# LCD.net
KiCad netlist of a schematic drawn in Altium Designer
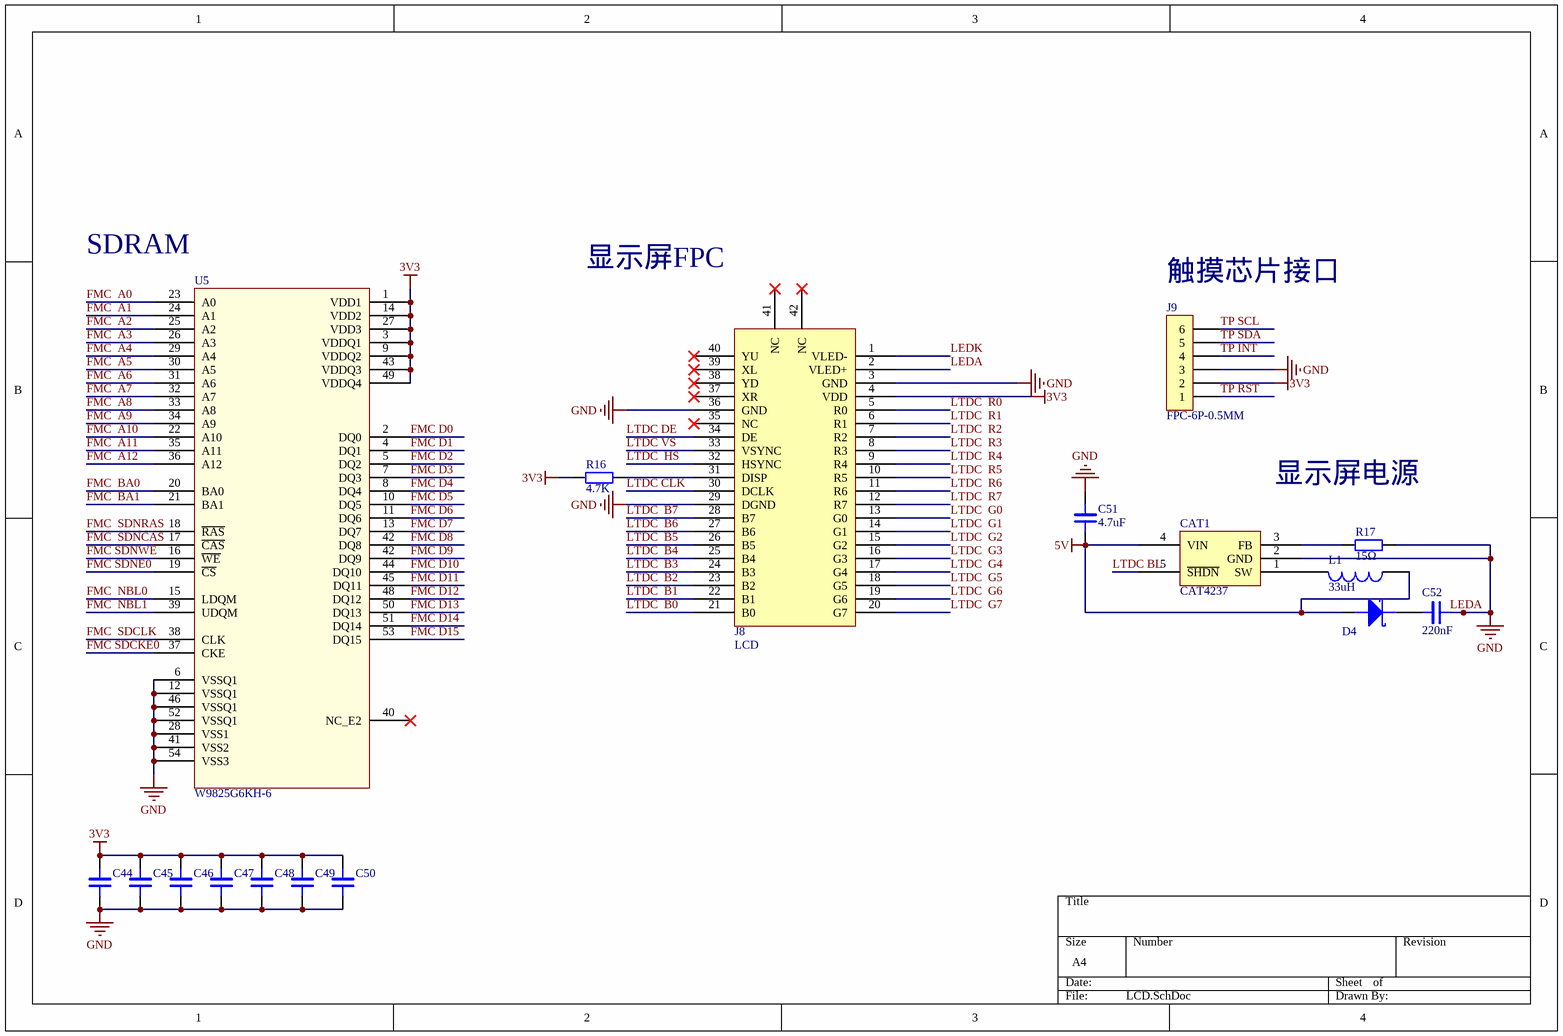
[diagram p0: LCD.SchDoc]

(export (version "E")
  (design (tool "Eeschema 10.0.6"))
  (components
    (comp (ref "C44")
      (value "100nF 16V")
      (footprint "0805")
      (description "Capacitor")
      (libsource (lib "General") (part "CAP"))
    )
    (comp (ref "C45")
      (value "100nF 16V")
      (footprint "0805")
      (description "Capacitor")
      (libsource (lib "General") (part "CAP"))
    )
    (comp (ref "C46")
      (value "100nF 16V")
      (footprint "0805")
      (description "Capacitor")
      (libsource (lib "General") (part "CAP"))
    )
    (comp (ref "C47")
      (value "100nF 16V")
      (footprint "0805")
      (description "Capacitor")
      (libsource (lib "General") (part "CAP"))
    )
    (comp (ref "C48")
      (value "100nF 16V")
      (footprint "0805")
      (description "Capacitor")
      (libsource (lib "General") (part "CAP"))
    )
    (comp (ref "C49")
      (value "100nF 16V")
      (footprint "0805")
      (description "Capacitor")
      (libsource (lib "General") (part "CAP"))
    )
    (comp (ref "C50")
      (value "100nF 16V")
      (footprint "0805")
      (description "Capacitor")
      (libsource (lib "General") (part "CAP"))
    )
    (comp (ref "C51")
      (value "4.7uF")
      (footprint "CAP-1812")
      (description "Capacitor")
      (libsource (lib "General") (part "CAP"))
    )
    (comp (ref "C52")
      (value "220nF")
      (footprint "CAP-1812")
      (description "Capacitor")
      (libsource (lib "General") (part "CAP"))
    )
    (comp (ref "CAT1")
      (value "CAT4237")
      (footprint "SOT-23-5")
      (libsource (lib "MainBoard") (part "CAT4237"))
    )
    (comp (ref "D4")
      (value "~")
      (footprint "DO-15")
      (description "肖特基二极管")
      (libsource (lib "二极管") (part "DIODE SCHOTTKY"))
    )
    (comp (ref "J8")
      (value "LCD")
      (description "FPC 接线口0.5mm 40Pins")
      (libsource (lib "MainBoard") (part "LCD"))
    )
    (comp (ref "J9")
      (value "FPC-6P-0.5MM")
      (footprint "Pin HDR1X6/2.54mm-S")
      (libsource (lib "排针") (part "Pin HDR1X6"))
    )
    (comp (ref "L1")
      (value "33uH")
      (footprint "AL0204")
      (description "INDUCTOR")
      (libsource (lib "电感") (part "INDUCTOR"))
    )
    (comp (ref "R16")
      (value "4.7K")
      (footprint "0805")
      (description "Resistor")
      (libsource (lib "General") (part "RES"))
    )
    (comp (ref "R17")
      (value "15Ω")
      (footprint "0805")
      (description "Resistor")
      (libsource (lib "General") (part "RES"))
    )
    (comp (ref "U5") (value "W9825G6KH-6") (libsource (lib "MainBoard") (part "W9825G6KH-6")))
  )
  (nets
    (net (code "1") (name "/FMC  A0") (class "Default")
      (node (ref "U5") (pin "23") (pinfunction "A0_23") (pintype "passive"))
    )
    (net (code "2") (name "/FMC  A1") (class "Default")
      (node (ref "U5") (pin "24") (pinfunction "A1_24") (pintype "passive"))
    )
    (net (code "3") (name "/FMC  A2") (class "Default")
      (node (ref "U5") (pin "25") (pinfunction "A2_25") (pintype "passive"))
    )
    (net (code "4") (name "/FMC  A3") (class "Default")
      (node (ref "U5") (pin "26") (pinfunction "A3_26") (pintype "passive"))
    )
    (net (code "5") (name "/FMC  A4") (class "Default")
      (node (ref "U5") (pin "29") (pinfunction "A4_29") (pintype "passive"))
    )
    (net (code "6") (name "/FMC  A5") (class "Default")
      (node (ref "U5") (pin "30") (pinfunction "A5_30") (pintype "passive"))
    )
    (net (code "7") (name "/FMC  A6") (class "Default")
      (node (ref "U5") (pin "31") (pinfunction "A6_31") (pintype "passive"))
    )
    (net (code "8") (name "/FMC  A7") (class "Default")
      (node (ref "U5") (pin "32") (pinfunction "A7_32") (pintype "passive"))
    )
    (net (code "9") (name "/FMC  A8") (class "Default")
      (node (ref "U5") (pin "33") (pinfunction "A8_33") (pintype "passive"))
    )
    (net (code "10") (name "/FMC  A9") (class "Default")
      (node (ref "U5") (pin "34") (pinfunction "A9_34") (pintype "passive"))
    )
    (net (code "11") (name "/FMC  A10") (class "Default")
      (node (ref "U5") (pin "22") (pinfunction "A10_22") (pintype "passive"))
    )
    (net (code "12") (name "/FMC  A11") (class "Default")
      (node (ref "U5") (pin "35") (pinfunction "A11_35") (pintype "passive"))
    )
    (net (code "13") (name "/FMC  A12") (class "Default")
      (node (ref "U5") (pin "36") (pinfunction "A12_36") (pintype "passive"))
    )
    (net (code "14") (name "/FMC  BA0") (class "Default")
      (node (ref "U5") (pin "20") (pinfunction "BA0_20") (pintype "passive"))
    )
    (net (code "15") (name "/FMC  BA1") (class "Default")
      (node (ref "U5") (pin "21") (pinfunction "BA1_21") (pintype "passive"))
    )
    (net (code "16") (name "/FMC  NBL0") (class "Default")
      (node (ref "U5") (pin "15") (pinfunction "LDQM_15") (pintype "passive"))
    )
    (net (code "17") (name "/FMC  NBL1") (class "Default")
      (node (ref "U5") (pin "39") (pinfunction "UDQM_39") (pintype "passive"))
    )
    (net (code "18") (name "/FMC  SDCLK") (class "Default")
      (node (ref "U5") (pin "38") (pinfunction "CLK_38") (pintype "passive"))
    )
    (net (code "19") (name "/FMC  SDNCAS") (class "Default")
      (node (ref "U5") (pin "17") (pinfunction "~{CAS}_17") (pintype "passive"))
    )
    (net (code "20") (name "/FMC  SDNRAS") (class "Default")
      (node (ref "U5") (pin "18") (pinfunction "~{RAS}_18") (pintype "passive"))
    )
    (net (code "21") (name "/FMC D0") (class "Default")
      (node (ref "U5") (pin "2") (pinfunction "DQ0_2") (pintype "passive"))
    )
    (net (code "22") (name "/FMC D1") (class "Default")
      (node (ref "U5") (pin "4") (pinfunction "DQ1_4") (pintype "passive"))
    )
    (net (code "23") (name "/FMC D2") (class "Default")
      (node (ref "U5") (pin "5") (pinfunction "DQ2_5") (pintype "passive"))
    )
    (net (code "24") (name "/FMC D3") (class "Default")
      (node (ref "U5") (pin "7") (pinfunction "DQ3_7") (pintype "passive"))
    )
    (net (code "25") (name "/FMC D4") (class "Default")
      (node (ref "U5") (pin "8") (pinfunction "DQ4_8") (pintype "passive"))
    )
    (net (code "26") (name "/FMC D5") (class "Default")
      (node (ref "U5") (pin "10") (pinfunction "DQ5_10") (pintype "passive"))
    )
    (net (code "27") (name "/FMC D6") (class "Default")
      (node (ref "U5") (pin "11") (pinfunction "DQ6_11") (pintype "passive"))
    )
    (net (code "28") (name "/FMC D7") (class "Default")
      (node (ref "U5") (pin "13") (pinfunction "DQ7_13") (pintype "passive"))
    )
    (net (code "29") (name "/FMC D8") (class "Default")
      (node (ref "U5") (pin "42") (pinfunction "DQ8_42") (pintype "passive"))
    )
    (net (code "30") (name "/FMC D9") (class "Default")
      (node (ref "U5") (pin "42") (pinfunction "DQ9_42") (pintype "passive"))
    )
    (net (code "31") (name "/FMC D10") (class "Default")
      (node (ref "U5") (pin "44") (pinfunction "DQ10_44") (pintype "passive"))
    )
    (net (code "32") (name "/FMC D11") (class "Default")
      (node (ref "U5") (pin "45") (pinfunction "DQ11_45") (pintype "passive"))
    )
    (net (code "33") (name "/FMC D12") (class "Default")
      (node (ref "U5") (pin "48") (pinfunction "DQ12_48") (pintype "passive"))
    )
    (net (code "34") (name "/FMC D13") (class "Default")
      (node (ref "U5") (pin "50") (pinfunction "DQ13_50") (pintype "passive"))
    )
    (net (code "35") (name "/FMC D14") (class "Default")
      (node (ref "U5") (pin "51") (pinfunction "DQ14_51") (pintype "passive"))
    )
    (net (code "36") (name "/FMC D15") (class "Default")
      (node (ref "U5") (pin "53") (pinfunction "DQ15_53") (pintype "passive"))
    )
    (net (code "37") (name "/FMC SDCKE0") (class "Default")
      (node (ref "U5") (pin "37") (pinfunction "CKE_37") (pintype "passive"))
    )
    (net (code "38") (name "/FMC SDNE0") (class "Default")
      (node (ref "U5") (pin "19") (pinfunction "~{CS}_19") (pintype "passive"))
    )
    (net (code "39") (name "/FMC SDNWE") (class "Default")
      (node (ref "U5") (pin "16") (pinfunction "~{WE}_16") (pintype "passive"))
    )
    (net (code "40") (name "/LEDK") (class "Default")
      (node (ref "J8") (pin "1") (pinfunction "VLED-_1") (pintype "passive"))
    )
    (net (code "41") (name "/LTDC  B0") (class "Default")
      (node (ref "J8") (pin "21") (pinfunction "B0_21") (pintype "passive"))
    )
    (net (code "42") (name "/LTDC  B1") (class "Default")
      (node (ref "J8") (pin "22") (pinfunction "B1_22") (pintype "passive"))
    )
    (net (code "43") (name "/LTDC  B2") (class "Default")
      (node (ref "J8") (pin "23") (pinfunction "B2_23") (pintype "passive"))
    )
    (net (code "44") (name "/LTDC  B3") (class "Default")
      (node (ref "J8") (pin "24") (pinfunction "B3_24") (pintype "passive"))
    )
    (net (code "45") (name "/LTDC  B4") (class "Default")
      (node (ref "J8") (pin "25") (pinfunction "B4_25") (pintype "passive"))
    )
    (net (code "46") (name "/LTDC  B5") (class "Default")
      (node (ref "J8") (pin "26") (pinfunction "B5_26") (pintype "passive"))
    )
    (net (code "47") (name "/LTDC  B6") (class "Default")
      (node (ref "J8") (pin "27") (pinfunction "B6_27") (pintype "passive"))
    )
    (net (code "48") (name "/LTDC  B7") (class "Default")
      (node (ref "J8") (pin "28") (pinfunction "B7_28") (pintype "passive"))
    )
    (net (code "49") (name "/LTDC  G0") (class "Default")
      (node (ref "J8") (pin "13") (pinfunction "G0_13") (pintype "passive"))
    )
    (net (code "50") (name "/LTDC  G1") (class "Default")
      (node (ref "J8") (pin "14") (pinfunction "G1_14") (pintype "passive"))
    )
    (net (code "51") (name "/LTDC  G2") (class "Default")
      (node (ref "J8") (pin "15") (pinfunction "G2_15") (pintype "passive"))
    )
    (net (code "52") (name "/LTDC  G3") (class "Default")
      (node (ref "J8") (pin "16") (pinfunction "G3_16") (pintype "passive"))
    )
    (net (code "53") (name "/LTDC  G4") (class "Default")
      (node (ref "J8") (pin "17") (pinfunction "G4_17") (pintype "passive"))
    )
    (net (code "54") (name "/LTDC  G5") (class "Default")
      (node (ref "J8") (pin "18") (pinfunction "G5_18") (pintype "passive"))
    )
    (net (code "55") (name "/LTDC  G6") (class "Default")
      (node (ref "J8") (pin "19") (pinfunction "G6_19") (pintype "passive"))
    )
    (net (code "56") (name "/LTDC  G7") (class "Default")
      (node (ref "J8") (pin "20") (pinfunction "G7_20") (pintype "passive"))
    )
    (net (code "57") (name "/LTDC  HS") (class "Default")
      (node (ref "J8") (pin "32") (pinfunction "HSYNC_32") (pintype "passive"))
    )
    (net (code "58") (name "/LTDC  R0") (class "Default")
      (node (ref "J8") (pin "5") (pinfunction "R0_5") (pintype "passive"))
    )
    (net (code "59") (name "/LTDC  R1") (class "Default")
      (node (ref "J8") (pin "6") (pinfunction "R1_6") (pintype "passive"))
    )
    (net (code "60") (name "/LTDC  R2") (class "Default")
      (node (ref "J8") (pin "7") (pinfunction "R2_7") (pintype "passive"))
    )
    (net (code "61") (name "/LTDC  R3") (class "Default")
      (node (ref "J8") (pin "8") (pinfunction "R3_8") (pintype "passive"))
    )
    (net (code "62") (name "/LTDC  R4") (class "Default")
      (node (ref "J8") (pin "9") (pinfunction "R4_9") (pintype "passive"))
    )
    (net (code "63") (name "/LTDC  R5") (class "Default")
      (node (ref "J8") (pin "10") (pinfunction "R5_10") (pintype "passive"))
    )
    (net (code "64") (name "/LTDC  R6") (class "Default")
      (node (ref "J8") (pin "11") (pinfunction "R6_11") (pintype "passive"))
    )
    (net (code "65") (name "/LTDC  R7") (class "Default")
      (node (ref "J8") (pin "12") (pinfunction "R7_12") (pintype "passive"))
    )
    (net (code "66") (name "/LTDC BL") (class "Default")
      (node (ref "CAT1") (pin "5") (pinfunction "~{SHDN}_5") (pintype "passive"))
    )
    (net (code "67") (name "/LTDC CLK") (class "Default")
      (node (ref "J8") (pin "30") (pinfunction "DCLK_30") (pintype "passive"))
    )
    (net (code "68") (name "/LTDC DE") (class "Default")
      (node (ref "J8") (pin "34") (pinfunction "DE_34") (pintype "passive"))
    )
    (net (code "69") (name "/LTDC VS") (class "Default")
      (node (ref "J8") (pin "33") (pinfunction "VSYNC_33") (pintype "passive"))
    )
    (net (code "70") (name "/TP INT") (class "Default")
      (node (ref "J9") (pin "4") (pinfunction "4_4") (pintype "passive"))
    )
    (net (code "71") (name "/TP RST") (class "Default")
      (node (ref "J9") (pin "1") (pinfunction "1_1") (pintype "passive"))
    )
    (net (code "72") (name "/TP SCL") (class "Default")
      (node (ref "J9") (pin "6") (pinfunction "6_6") (pintype "passive"))
    )
    (net (code "73") (name "/TP SDA") (class "Default")
      (node (ref "J9") (pin "5") (pinfunction "5_5") (pintype "passive"))
    )
    (net (code "74") (name "3V3") (class "Default")
      (node (ref "C44") (pin "2") (pinfunction "2_2") (pintype "passive"))
      (node (ref "C45") (pin "2") (pinfunction "2_2") (pintype "passive"))
      (node (ref "C46") (pin "2") (pinfunction "2_2") (pintype "passive"))
      (node (ref "C47") (pin "2") (pinfunction "2_2") (pintype "passive"))
      (node (ref "C48") (pin "2") (pinfunction "2_2") (pintype "passive"))
      (node (ref "C49") (pin "2") (pinfunction "2_2") (pintype "passive"))
      (node (ref "C50") (pin "2") (pinfunction "2_2") (pintype "passive"))
      (node (ref "J8") (pin "4") (pinfunction "VDD_4") (pintype "passive"))
      (node (ref "J9") (pin "2") (pinfunction "2_2") (pintype "passive"))
      (node (ref "R16") (pin "1") (pinfunction "1_1") (pintype "passive"))
      (node (ref "U5") (pin "1") (pinfunction "VDD1_1") (pintype "passive"))
      (node (ref "U5") (pin "14") (pinfunction "VDD2_14") (pintype "passive"))
      (node (ref "U5") (pin "27") (pinfunction "VDD3_27") (pintype "passive"))
      (node (ref "U5") (pin "3") (pinfunction "VDDQ1_3") (pintype "passive"))
      (node (ref "U5") (pin "43") (pinfunction "VDDQ3_43") (pintype "passive"))
      (node (ref "U5") (pin "49") (pinfunction "VDDQ4_49") (pintype "passive"))
      (node (ref "U5") (pin "9") (pinfunction "VDDQ2_9") (pintype "passive"))
    )
    (net (code "75") (name "5V") (class "Default")
      (node (ref "C51") (pin "1") (pinfunction "1_1") (pintype "passive"))
      (node (ref "CAT1") (pin "4") (pinfunction "VIN_4") (pintype "passive"))
      (node (ref "D4") (pin "A") (pinfunction "A_A") (pintype "passive"))
      (node (ref "L1") (pin "1") (pinfunction "1_1") (pintype "passive"))
    )
    (net (code "76") (name "GND") (class "Default")
      (node (ref "C44") (pin "1") (pinfunction "1_1") (pintype "passive"))
      (node (ref "C45") (pin "1") (pinfunction "1_1") (pintype "passive"))
      (node (ref "C46") (pin "1") (pinfunction "1_1") (pintype "passive"))
      (node (ref "C47") (pin "1") (pinfunction "1_1") (pintype "passive"))
      (node (ref "C48") (pin "1") (pinfunction "1_1") (pintype "passive"))
      (node (ref "C49") (pin "1") (pinfunction "1_1") (pintype "passive"))
      (node (ref "C50") (pin "1") (pinfunction "1_1") (pintype "passive"))
      (node (ref "C51") (pin "2") (pinfunction "2_2") (pintype "passive"))
      (node (ref "C52") (pin "2") (pinfunction "2_2") (pintype "passive"))
      (node (ref "CAT1") (pin "2") (pinfunction "GND_2") (pintype "passive"))
      (node (ref "J8") (pin "2") (pinfunction "VLED+_2") (pintype "passive"))
      (node (ref "J8") (pin "29") (pinfunction "DGND_29") (pintype "passive"))
      (node (ref "J8") (pin "3") (pinfunction "GND_3") (pintype "passive"))
      (node (ref "J8") (pin "36") (pinfunction "GND_36") (pintype "passive"))
      (node (ref "J9") (pin "3") (pinfunction "3_3") (pintype "passive"))
      (node (ref "R17") (pin "2") (pinfunction "2_2") (pintype "passive"))
      (node (ref "U5") (pin "12") (pinfunction "VSSQ1_12") (pintype "passive"))
      (node (ref "U5") (pin "28") (pinfunction "VSS1_28") (pintype "passive"))
      (node (ref "U5") (pin "41") (pinfunction "VSS2_41") (pintype "passive"))
      (node (ref "U5") (pin "46") (pinfunction "VSSQ1_46") (pintype "passive"))
      (node (ref "U5") (pin "52") (pinfunction "VSSQ1_52") (pintype "passive"))
      (node (ref "U5") (pin "54") (pinfunction "VSS3_54") (pintype "passive"))
      (node (ref "U5") (pin "6") (pinfunction "VSSQ1_6") (pintype "passive"))
    )
    (net (code "77") (name "Net-(C52-Pad1)") (class "Default")
      (node (ref "C52") (pin "1") (pinfunction "1_1") (pintype "passive"))
      (node (ref "D4") (pin "K") (pinfunction "K_K") (pintype "passive"))
    )
    (net (code "78") (name "Net-(CAT1-FB)") (class "Default")
      (node (ref "CAT1") (pin "3") (pinfunction "FB_3") (pintype "passive"))
      (node (ref "R17") (pin "1") (pinfunction "1_1") (pintype "passive"))
    )
    (net (code "79") (name "Net-(CAT1-SW)") (class "Default")
      (node (ref "CAT1") (pin "1") (pinfunction "SW_1") (pintype "passive"))
      (node (ref "L1") (pin "2") (pinfunction "2_2") (pintype "passive"))
    )
    (net (code "80") (name "Net-(J8-DISP)") (class "Default")
      (node (ref "J8") (pin "31") (pinfunction "DISP_31") (pintype "passive"))
      (node (ref "R16") (pin "2") (pinfunction "2_2") (pintype "passive"))
    )
    (net (code "81") (name "unconnected-(J8-NC-Pad35)") (class "Default")
      (node (ref "J8") (pin "35") (pinfunction "NC_35") (pintype "passive+no_connect"))
    )
    (net (code "82") (name "unconnected-(J8-NC-Pad41)") (class "Default")
      (node (ref "J8") (pin "41") (pinfunction "NC_41") (pintype "passive+no_connect"))
    )
    (net (code "83") (name "unconnected-(J8-NC-Pad42)") (class "Default")
      (node (ref "J8") (pin "42") (pinfunction "NC_42") (pintype "passive+no_connect"))
    )
    (net (code "84") (name "unconnected-(J8-XL-Pad39)") (class "Default")
      (node (ref "J8") (pin "39") (pinfunction "XL_39") (pintype "passive+no_connect"))
    )
    (net (code "85") (name "unconnected-(J8-XR-Pad37)") (class "Default")
      (node (ref "J8") (pin "37") (pinfunction "XR_37") (pintype "passive+no_connect"))
    )
    (net (code "86") (name "unconnected-(J8-YD-Pad38)") (class "Default")
      (node (ref "J8") (pin "38") (pinfunction "YD_38") (pintype "passive+no_connect"))
    )
    (net (code "87") (name "unconnected-(J8-YU-Pad40)") (class "Default")
      (node (ref "J8") (pin "40") (pinfunction "YU_40") (pintype "passive+no_connect"))
    )
    (net (code "88") (name "unconnected-(U5-NC_E2-Pad40)") (class "Default")
      (node (ref "U5") (pin "40") (pinfunction "NC_E2_40") (pintype "passive+no_connect"))
    )
  )
)
